# MainCircuitSchematic.net
KiCad netlist of a schematic drawn in EAGLE
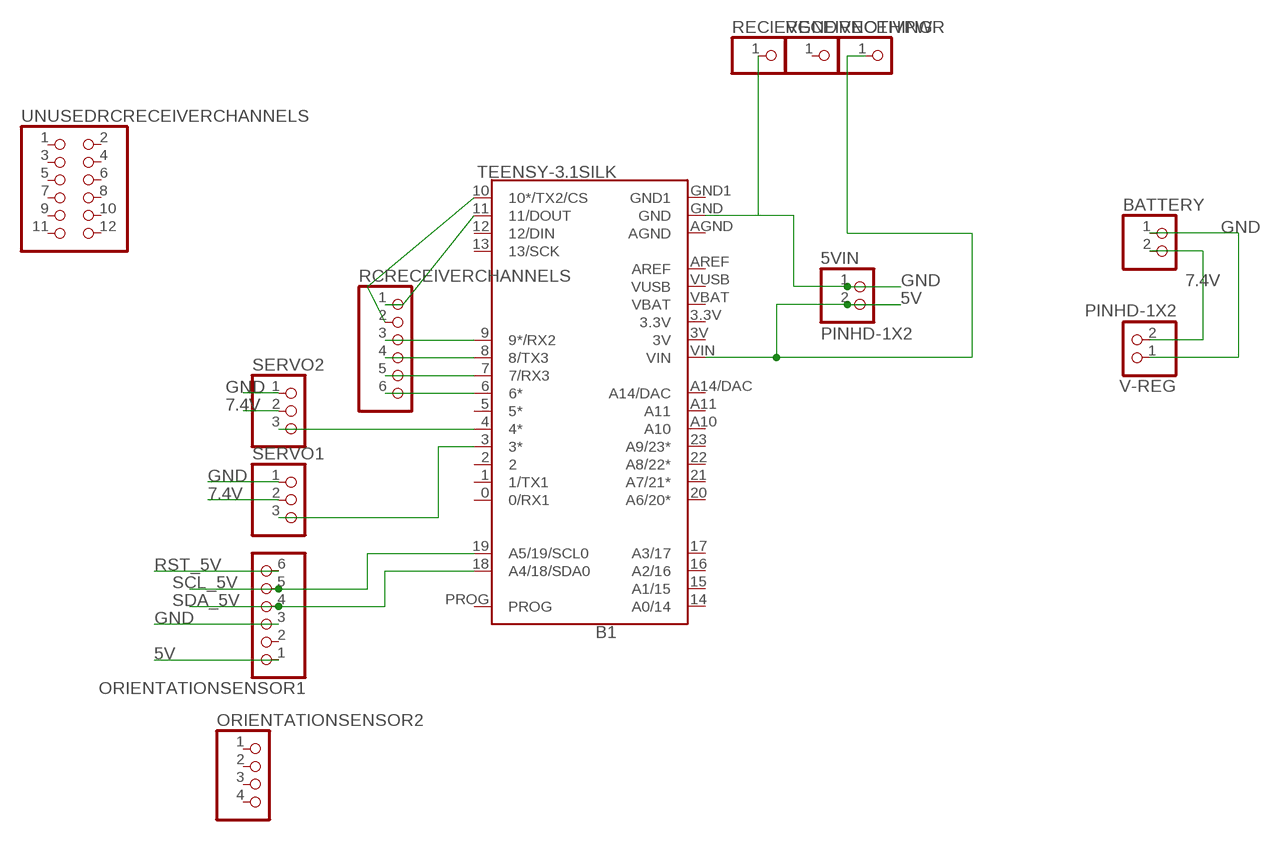
[diagram p0: schematic, sheet 1]

(export (version "E")
  (design (tool "Eeschema 10.0.6"))
  (components
    (comp (ref "5VIN")
      (value "PINHD-1X2")
      (footprint "eagle-import:1X02")
      (libsource (lib "eagle-import") (part "PINHD-1X2"))
    )
    (comp (ref "B1")
      (value "TEENSY-3.1SILK")
      (footprint "eagle-import:TEENSY-3.1")
      (libsource (lib "eagle-import") (part "TEENSY-3.1SILK"))
    )
    (comp (ref "BATTERY")
      (value "PINHD-1X2")
      (footprint "eagle-import:1X02")
      (libsource (lib "eagle-import") (part "PINHD-1X2"))
    )
    (comp (ref "ORIENTATIONSENSOR1")
      (value "HEADER-1X676MIL")
      (footprint "eagle-import:1X06_ROUND_76")
      (libsource (lib "eagle-import") (part "HEADER-1X676MIL"))
    )
    (comp (ref "ORIENTATIONSENSOR2")
      (value "HEADER-1X476MIL")
      (footprint "eagle-import:1X04_ROUND_76")
      (libsource (lib "eagle-import") (part "HEADER-1X476MIL"))
    )
    (comp (ref "RCRECEIVERCHANNELS")
      (value "PINHD-1X6")
      (footprint "eagle-import:1X06")
      (libsource (lib "eagle-import") (part "PINHD-1X6"))
    )
    (comp (ref "RECEIVNOTHING")
      (value "PINHD-1X1")
      (footprint "eagle-import:1X01")
      (libsource (lib "eagle-import") (part "PINHD-1X1"))
    )
    (comp (ref "RECEIVPWR")
      (value "PINHD-1X1")
      (footprint "eagle-import:1X01")
      (libsource (lib "eagle-import") (part "PINHD-1X1"))
    )
    (comp (ref "RECIEVGND")
      (value "PINHD-1X1")
      (footprint "eagle-import:1X01")
      (libsource (lib "eagle-import") (part "PINHD-1X1"))
    )
    (comp (ref "SERVO1")
      (value "PINHD-1X3CB")
      (footprint "eagle-import:1X03-CLEANBIG")
      (libsource (lib "eagle-import") (part "PINHD-1X3CB"))
    )
    (comp (ref "SERVO2")
      (value "PINHD-1X3CB")
      (footprint "eagle-import:1X03-CLEANBIG")
      (libsource (lib "eagle-import") (part "PINHD-1X3CB"))
    )
    (comp (ref "UNUSEDRCRECEIVERCHANNELS")
      (value "PINHD-2X6")
      (footprint "eagle-import:2X06")
      (libsource (lib "eagle-import") (part "PINHD-2X6"))
    )
    (comp (ref "V-REG")
      (value "PINHD-1X2")
      (footprint "eagle-import:1X02")
      (libsource (lib "eagle-import") (part "PINHD-1X2"))
    )
  )
  (nets
    (net (code "1") (name "/3.3V") (class "Default")
      (node (ref "B1") (pin "3.3V") (pinfunction "3.3V_3.3V") (pintype "power_in"))
    )
    (net (code "2") (name "/3V") (class "Default")
      (node (ref "B1") (pin "3V") (pinfunction "3V_3V") (pintype "power_in"))
    )
    (net (code "3") (name "/5V") (class "Default")
      (node (ref "5VIN") (pin "2") (pinfunction "2_2") (pintype "passive"))
      (node (ref "B1") (pin "VIN") (pinfunction "VIN_VIN") (pintype "power_in"))
      (node (ref "ORIENTATIONSENSOR1") (pin "1") (pinfunction "1_1") (pintype "passive"))
      (node (ref "RECEIVPWR") (pin "1") (pinfunction "1_1") (pintype "passive"))
    )
    (net (code "4") (name "/7.4V") (class "Default")
      (node (ref "BATTERY") (pin "2") (pinfunction "2_2") (pintype "passive"))
      (node (ref "SERVO1") (pin "2") (pinfunction "2_2") (pintype "passive"))
      (node (ref "SERVO2") (pin "2") (pinfunction "2_2") (pintype "passive"))
      (node (ref "V-REG") (pin "2") (pinfunction "2_2") (pintype "passive"))
    )
    (net (code "5") (name "/AGND") (class "Default")
      (node (ref "B1") (pin "AGND") (pinfunction "AGND_AGND") (pintype "power_in"))
    )
    (net (code "6") (name "/GND") (class "Default")
      (node (ref "5VIN") (pin "1") (pinfunction "1_1") (pintype "passive"))
      (node (ref "B1") (pin "GND") (pinfunction "GND_GND") (pintype "power_in"))
      (node (ref "BATTERY") (pin "1") (pinfunction "1_1") (pintype "passive"))
      (node (ref "ORIENTATIONSENSOR1") (pin "3") (pinfunction "3_3") (pintype "passive"))
      (node (ref "RECIEVGND") (pin "1") (pinfunction "1_1") (pintype "passive"))
      (node (ref "SERVO1") (pin "1") (pinfunction "1_1") (pintype "passive"))
      (node (ref "SERVO2") (pin "1") (pinfunction "1_1") (pintype "passive"))
      (node (ref "V-REG") (pin "1") (pinfunction "1_1") (pintype "passive"))
    )
    (net (code "7") (name "/GND1") (class "Default")
      (node (ref "B1") (pin "GND1") (pinfunction "GND1_GND1") (pintype "power_in"))
    )
    (net (code "8") (name "/RST_5V") (class "Default")
      (node (ref "ORIENTATIONSENSOR1") (pin "6") (pinfunction "6_6") (pintype "passive"))
    )
    (net (code "9") (name "/SCL_5V") (class "Default")
      (node (ref "B1") (pin "19") (pinfunction "A5/19/SCL0_19") (pintype "bidirectional"))
      (node (ref "ORIENTATIONSENSOR1") (pin "5") (pinfunction "5_5") (pintype "passive"))
    )
    (net (code "10") (name "/SDA_5V") (class "Default")
      (node (ref "B1") (pin "18") (pinfunction "A4/18/SDA0_18") (pintype "bidirectional"))
      (node (ref "ORIENTATIONSENSOR1") (pin "4") (pinfunction "4_4") (pintype "passive"))
    )
    (net (code "11") (name "/VBAT") (class "Default")
      (node (ref "B1") (pin "VBAT") (pinfunction "VBAT_VBAT") (pintype "power_in"))
    )
    (net (code "12") (name "/VUSB") (class "Default")
      (node (ref "B1") (pin "VUSB") (pinfunction "VUSB_VUSB") (pintype "power_in"))
    )
    (net (code "13") (name "Net-(B1-3*)") (class "Default")
      (node (ref "B1") (pin "3") (pinfunction "3*_3") (pintype "bidirectional"))
      (node (ref "SERVO1") (pin "3") (pinfunction "3_3") (pintype "passive"))
    )
    (net (code "14") (name "Net-(B1-4*)") (class "Default")
      (node (ref "B1") (pin "4") (pinfunction "4*_4") (pintype "bidirectional"))
      (node (ref "SERVO2") (pin "3") (pinfunction "3_3") (pintype "passive"))
    )
    (net (code "15") (name "Net-(B1-6*)") (class "Default")
      (node (ref "B1") (pin "6") (pinfunction "6*_6") (pintype "bidirectional"))
      (node (ref "RCRECEIVERCHANNELS") (pin "6") (pinfunction "6_6") (pintype "passive"))
    )
    (net (code "16") (name "Net-(B1-7{slash}RX3)") (class "Default")
      (node (ref "B1") (pin "7") (pinfunction "7/RX3_7") (pintype "bidirectional"))
      (node (ref "RCRECEIVERCHANNELS") (pin "5") (pinfunction "5_5") (pintype "passive"))
    )
    (net (code "17") (name "Net-(B1-8{slash}TX3)") (class "Default")
      (node (ref "B1") (pin "8") (pinfunction "8/TX3_8") (pintype "bidirectional"))
      (node (ref "RCRECEIVERCHANNELS") (pin "4") (pinfunction "4_4") (pintype "passive"))
    )
    (net (code "18") (name "Net-(B1-9*{slash}RX2)") (class "Default")
      (node (ref "B1") (pin "9") (pinfunction "9*/RX2_9") (pintype "bidirectional"))
      (node (ref "RCRECEIVERCHANNELS") (pin "3") (pinfunction "3_3") (pintype "passive"))
    )
    (net (code "19") (name "Net-(B1-10*{slash}TX2{slash}CS)") (class "Default")
      (node (ref "B1") (pin "10") (pinfunction "10*/TX2/CS_10") (pintype "bidirectional"))
      (node (ref "RCRECEIVERCHANNELS") (pin "2") (pinfunction "2_2") (pintype "passive"))
    )
    (net (code "20") (name "Net-(B1-11{slash}DOUT)") (class "Default")
      (node (ref "B1") (pin "11") (pinfunction "11/DOUT_11") (pintype "bidirectional"))
      (node (ref "RCRECEIVERCHANNELS") (pin "1") (pinfunction "1_1") (pintype "passive"))
    )
    (net (code "21") (name "unconnected-(B1-0{slash}RX1-Pad0)") (class "Default")
      (node (ref "B1") (pin "0") (pinfunction "0/RX1_0") (pintype "bidirectional"))
    )
    (net (code "22") (name "unconnected-(B1-1{slash}TX1-Pad1)") (class "Default")
      (node (ref "B1") (pin "1") (pinfunction "1/TX1_1") (pintype "bidirectional"))
    )
    (net (code "23") (name "unconnected-(B1-5*-Pad5)") (class "Default")
      (node (ref "B1") (pin "5") (pinfunction "5*_5") (pintype "bidirectional"))
    )
    (net (code "24") (name "unconnected-(B1-12{slash}DIN-Pad12)") (class "Default")
      (node (ref "B1") (pin "12") (pinfunction "12/DIN_12") (pintype "bidirectional"))
    )
    (net (code "25") (name "unconnected-(B1-13{slash}SCK-Pad13)") (class "Default")
      (node (ref "B1") (pin "13") (pinfunction "13/SCK_13") (pintype "bidirectional"))
    )
    (net (code "26") (name "unconnected-(B1-A0{slash}14-Pad14)") (class "Default")
      (node (ref "B1") (pin "14") (pinfunction "A0/14_14") (pintype "bidirectional"))
    )
    (net (code "27") (name "unconnected-(B1-A1{slash}15-Pad15)") (class "Default")
      (node (ref "B1") (pin "15") (pinfunction "A1/15_15") (pintype "bidirectional"))
    )
    (net (code "28") (name "unconnected-(B1-A2{slash}16-Pad16)") (class "Default")
      (node (ref "B1") (pin "16") (pinfunction "A2/16_16") (pintype "bidirectional"))
    )
    (net (code "29") (name "unconnected-(B1-A3{slash}17-Pad17)") (class "Default")
      (node (ref "B1") (pin "17") (pinfunction "A3/17_17") (pintype "bidirectional"))
    )
    (net (code "30") (name "unconnected-(B1-A6{slash}20*-Pad20)") (class "Default")
      (node (ref "B1") (pin "20") (pinfunction "A6/20*_20") (pintype "bidirectional"))
    )
    (net (code "31") (name "unconnected-(B1-A7{slash}21*-Pad21)") (class "Default")
      (node (ref "B1") (pin "21") (pinfunction "A7/21*_21") (pintype "bidirectional"))
    )
    (net (code "32") (name "unconnected-(B1-A8{slash}22*-Pad22)") (class "Default")
      (node (ref "B1") (pin "22") (pinfunction "A8/22*_22") (pintype "bidirectional"))
    )
    (net (code "33") (name "unconnected-(B1-A9{slash}23*-Pad23)") (class "Default")
      (node (ref "B1") (pin "23") (pinfunction "A9/23*_23") (pintype "bidirectional"))
    )
    (net (code "34") (name "unconnected-(B1-Pad2)") (class "Default")
      (node (ref "B1") (pin "2") (pinfunction "2_2") (pintype "bidirectional"))
    )
    (net (code "35") (name "unconnected-(B1-PadA10)") (class "Default")
      (node (ref "B1") (pin "A10") (pinfunction "A10_A10") (pintype "bidirectional"))
    )
    (net (code "36") (name "unconnected-(B1-PadA11)") (class "Default")
      (node (ref "B1") (pin "A11") (pinfunction "A11_A11") (pintype "bidirectional"))
    )
    (net (code "37") (name "unconnected-(B1-PadA14{slash}DAC)") (class "Default")
      (node (ref "B1") (pin "A14/DAC") (pinfunction "A14/DAC_A14/DAC") (pintype "bidirectional"))
    )
    (net (code "38") (name "unconnected-(B1-PadAREF)") (class "Default")
      (node (ref "B1") (pin "AREF") (pinfunction "AREF_AREF") (pintype "bidirectional"))
    )
    (net (code "39") (name "unconnected-(B1-PadPROG)") (class "Default")
      (node (ref "B1") (pin "PROG") (pinfunction "PROG_PROG") (pintype "bidirectional"))
    )
    (net (code "40") (name "unconnected-(ORIENTATIONSENSOR1-Pad2)") (class "Default")
      (node (ref "ORIENTATIONSENSOR1") (pin "2") (pinfunction "2_2") (pintype "passive"))
    )
    (net (code "41") (name "unconnected-(ORIENTATIONSENSOR2-Pad1)") (class "Default")
      (node (ref "ORIENTATIONSENSOR2") (pin "1") (pinfunction "1_1") (pintype "passive"))
    )
    (net (code "42") (name "unconnected-(ORIENTATIONSENSOR2-Pad2)") (class "Default")
      (node (ref "ORIENTATIONSENSOR2") (pin "2") (pinfunction "2_2") (pintype "passive"))
    )
    (net (code "43") (name "unconnected-(ORIENTATIONSENSOR2-Pad3)") (class "Default")
      (node (ref "ORIENTATIONSENSOR2") (pin "3") (pinfunction "3_3") (pintype "passive"))
    )
    (net (code "44") (name "unconnected-(ORIENTATIONSENSOR2-Pad4)") (class "Default")
      (node (ref "ORIENTATIONSENSOR2") (pin "4") (pinfunction "4_4") (pintype "passive"))
    )
    (net (code "45") (name "unconnected-(RECEIVNOTHING-Pad1)") (class "Default")
      (node (ref "RECEIVNOTHING") (pin "1") (pinfunction "1_1") (pintype "passive"))
    )
    (net (code "46") (name "unconnected-(UNUSEDRCRECEIVERCHANNELS-Pad1)") (class "Default")
      (node (ref "UNUSEDRCRECEIVERCHANNELS") (pin "1") (pinfunction "1_1") (pintype "passive"))
    )
    (net (code "47") (name "unconnected-(UNUSEDRCRECEIVERCHANNELS-Pad2)") (class "Default")
      (node (ref "UNUSEDRCRECEIVERCHANNELS") (pin "2") (pinfunction "2_2") (pintype "passive"))
    )
    (net (code "48") (name "unconnected-(UNUSEDRCRECEIVERCHANNELS-Pad3)") (class "Default")
      (node (ref "UNUSEDRCRECEIVERCHANNELS") (pin "3") (pinfunction "3_3") (pintype "passive"))
    )
    (net (code "49") (name "unconnected-(UNUSEDRCRECEIVERCHANNELS-Pad4)") (class "Default")
      (node (ref "UNUSEDRCRECEIVERCHANNELS") (pin "4") (pinfunction "4_4") (pintype "passive"))
    )
    (net (code "50") (name "unconnected-(UNUSEDRCRECEIVERCHANNELS-Pad5)") (class "Default")
      (node (ref "UNUSEDRCRECEIVERCHANNELS") (pin "5") (pinfunction "5_5") (pintype "passive"))
    )
    (net (code "51") (name "unconnected-(UNUSEDRCRECEIVERCHANNELS-Pad6)") (class "Default")
      (node (ref "UNUSEDRCRECEIVERCHANNELS") (pin "6") (pinfunction "6_6") (pintype "passive"))
    )
    (net (code "52") (name "unconnected-(UNUSEDRCRECEIVERCHANNELS-Pad7)") (class "Default")
      (node (ref "UNUSEDRCRECEIVERCHANNELS") (pin "7") (pinfunction "7_7") (pintype "passive"))
    )
    (net (code "53") (name "unconnected-(UNUSEDRCRECEIVERCHANNELS-Pad8)") (class "Default")
      (node (ref "UNUSEDRCRECEIVERCHANNELS") (pin "8") (pinfunction "8_8") (pintype "passive"))
    )
    (net (code "54") (name "unconnected-(UNUSEDRCRECEIVERCHANNELS-Pad9)") (class "Default")
      (node (ref "UNUSEDRCRECEIVERCHANNELS") (pin "9") (pinfunction "9_9") (pintype "passive"))
    )
    (net (code "55") (name "unconnected-(UNUSEDRCRECEIVERCHANNELS-Pad10)") (class "Default")
      (node (ref "UNUSEDRCRECEIVERCHANNELS") (pin "10") (pinfunction "10_10") (pintype "passive"))
    )
    (net (code "56") (name "unconnected-(UNUSEDRCRECEIVERCHANNELS-Pad11)") (class "Default")
      (node (ref "UNUSEDRCRECEIVERCHANNELS") (pin "11") (pinfunction "11_11") (pintype "passive"))
    )
    (net (code "57") (name "unconnected-(UNUSEDRCRECEIVERCHANNELS-Pad12)") (class "Default")
      (node (ref "UNUSEDRCRECEIVERCHANNELS") (pin "12") (pinfunction "12_12") (pintype "passive"))
    )
  )
)
